# dcb_top.net
KiCad netlist of a schematic drawn in Altium Designer
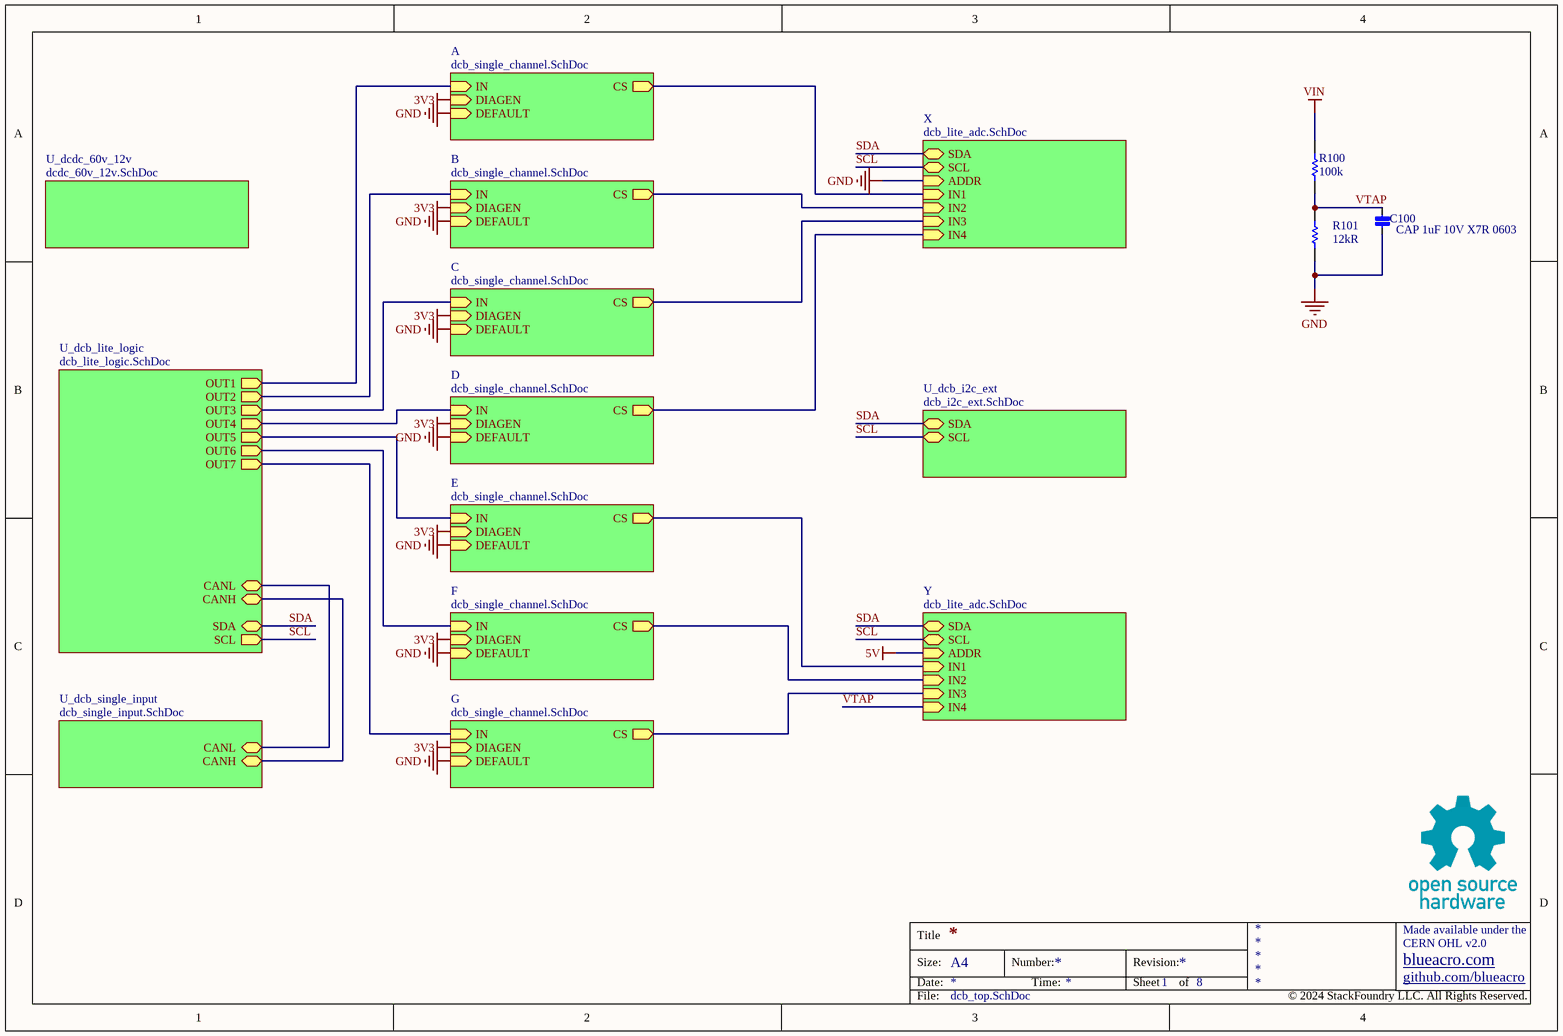
[diagram p0: dcb_top.SchDoc]

(export (version "E")
  (design (tool "Eeschema 10.0.6"))
  (components
    (comp (ref "C100")
      (value "CAP 1uF 10V X7R 0603")
      (footprint "FP-CL10-IPC_B")
      (description "Cap Ceramic 1uF 10V X7R 10% SMD 0603 125C Paper T/R")
      (libsource (lib "StackFoundry LLC") (part "C-EU"))
    )
    (comp (ref "R100")
      (value "100k")
      (footprint "RESC1608-IPC-LL")
      (description "SMD Chip Resistor, 100 kOhm, ± 1%, 100 mW, 0603 [1608 Metric], Thick Film, General Purpose")
      (fields (field (name "TOLERANCE") "1%") (field (name "Comment") "100k 0603 1%"))
      (libsource (lib "StackFoundry LLC") (part "RES"))
    )
    (comp (ref "R101")
      (value "12kR")
      (footprint "RESC1608X55X25LL10T15")
      (description "SMD Chip Resistor, 12 kOhm, ± 1%, 100 mW, 0603 [1608 Metric], Thick Film, General Purpose")
      (fields (field (name "TOLERANCE") "1%") (field (name "Comment") "12k 0603 1%"))
      (libsource (lib "StackFoundry LLC") (part "RES-2"))
    )
  )
  (nets
    (net (code "19") (name "/VTAP") (class "Default")
      (node (ref "C100") (pin "1") (pinfunction "1_1") (pintype "passive"))
      (node (ref "R100") (pin "1") (pinfunction "1_1") (pintype "passive"))
      (node (ref "R101") (pin "2") (pinfunction "2_2") (pintype "passive"))
    )
    (net (code "22") (name "GND") (class "Default")
      (node (ref "C100") (pin "2") (pinfunction "2_2") (pintype "passive"))
      (node (ref "R101") (pin "1") (pinfunction "1_1") (pintype "passive"))
    )
    (net (code "23") (name "VIN") (class "Default")
      (node (ref "R100") (pin "2") (pinfunction "2_2") (pintype "passive"))
    )
  )
)
